# AC_Voltage_Sampling.net
KiCad netlist of a schematic drawn in Altium Designer
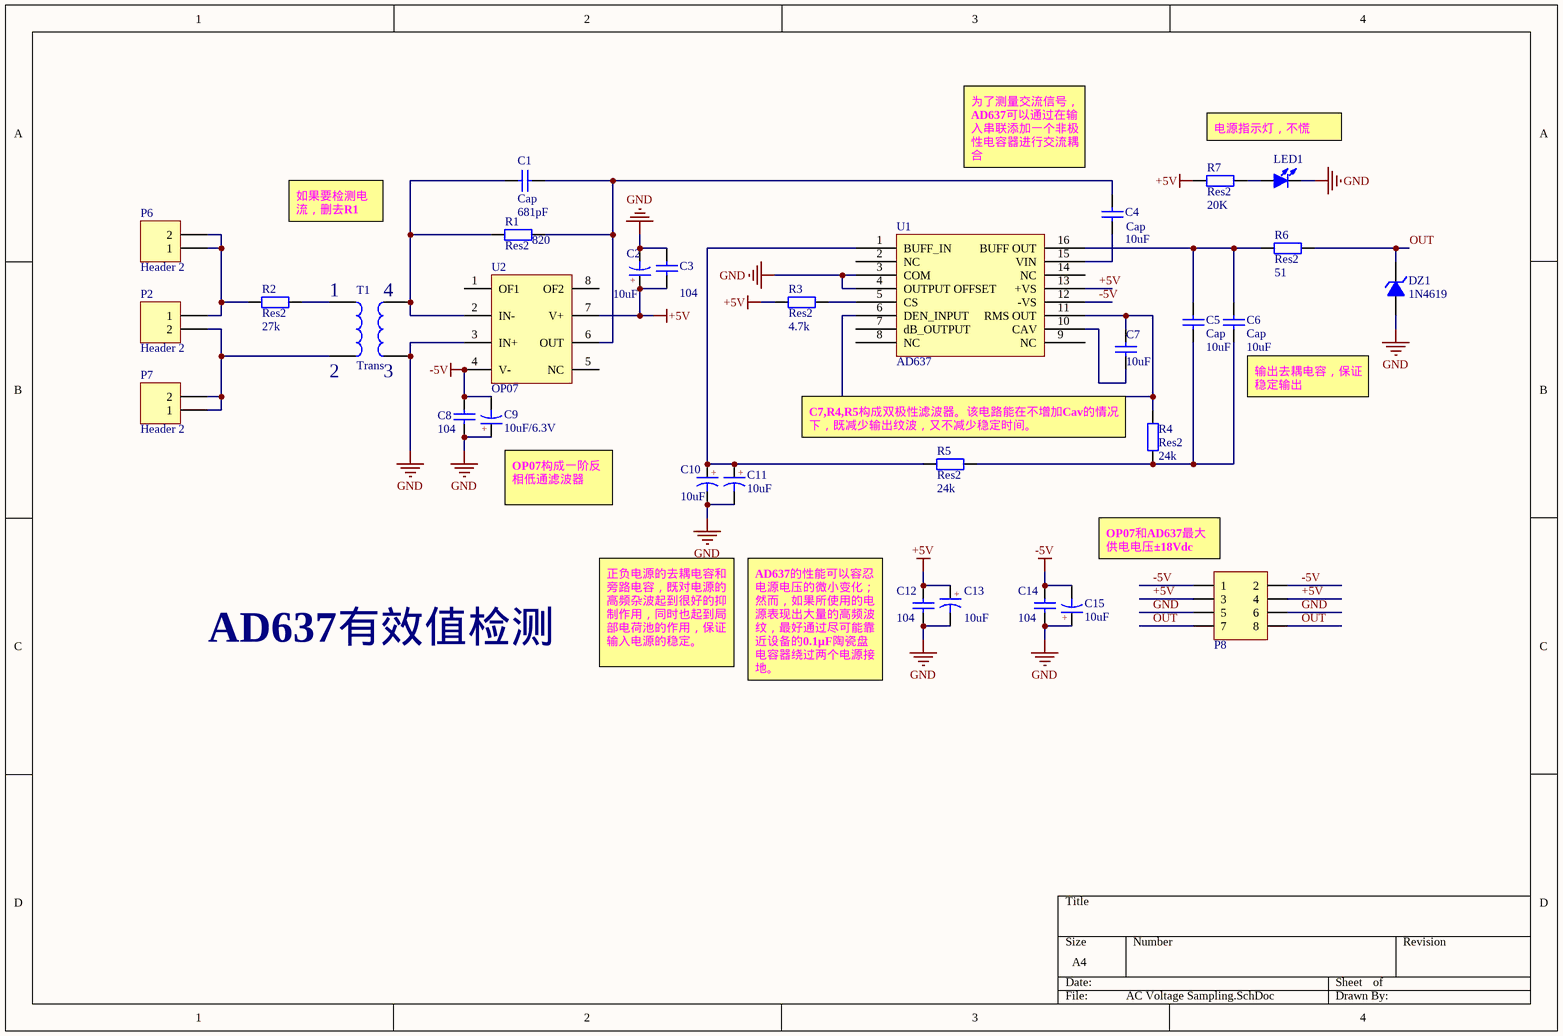
[diagram p0: AC Voltage Sampling.SchDoc]

(export (version "E")
  (design (tool "Eeschema 10.0.6"))
  (components
    (comp (ref "C1")
      (value "Cap")
      (footprint "C0805_L")
      (description "Capacitor")
      (fields (field (name "ALTIUM_VALUE") "681pF") (field (name "PUBLISHER") "Altium Limited"))
      (libsource (lib "Miscellaneous Devices") (part "Cap"))
    )
    (comp (ref "C2")
      (value "10uF")
      (footprint "C_3528")
      (description "贴片钽电容")
      (libsource (lib "0.1 - 电阻-电容-电感-磁珠-电位器") (part "CT"))
    )
    (comp (ref "C3")
      (value "104")
      (footprint "C0805_L")
      (description "Capacitor")
      (fields (field (name "Comment") "Cap") (field (name "PUBLISHER") "Altium Limited"))
      (libsource (lib "Miscellaneous Devices") (part "Cap"))
    )
    (comp (ref "C4")
      (value "Cap")
      (footprint "C0805_L")
      (description "Capacitor")
      (fields (field (name "ALTIUM_VALUE") "10uF") (field (name "PUBLISHER") "Altium Limited"))
      (libsource (lib "Miscellaneous Devices") (part "Cap"))
    )
    (comp (ref "C5")
      (value "Cap")
      (footprint "C0805_L")
      (description "Capacitor")
      (fields (field (name "ALTIUM_VALUE") "10uF") (field (name "PUBLISHER") "Altium Limited"))
      (libsource (lib "Miscellaneous Devices") (part "Cap"))
    )
    (comp (ref "C6")
      (value "Cap")
      (footprint "C0805_L")
      (description "Capacitor")
      (fields (field (name "ALTIUM_VALUE") "10uF") (field (name "PUBLISHER") "Altium Limited"))
      (libsource (lib "Miscellaneous Devices") (part "Cap"))
    )
    (comp (ref "C7")
      (value "10uF")
      (footprint "C0805_L")
      (description "Capacitor")
      (fields (field (name "Comment") "Cap") (field (name "PUBLISHER") "Altium Limited"))
      (libsource (lib "Miscellaneous Devices") (part "Cap"))
    )
    (comp (ref "C8")
      (value "104")
      (footprint "C0805_L")
      (description "Capacitor")
      (fields (field (name "Comment") "Cap") (field (name "PUBLISHER") "Altium Limited"))
      (libsource (lib "Miscellaneous Devices") (part "Cap"))
    )
    (comp (ref "C9")
      (value "10uF/6.3V")
      (footprint "C_3528")
      (description "贴片钽电容")
      (libsource (lib "0.1 - 电阻-电容-电感-磁珠-电位器") (part "CT"))
    )
    (comp (ref "C10")
      (value "10uF")
      (footprint "C_3528")
      (description "贴片钽电容")
      (libsource (lib "0.1 - 电阻-电容-电感-磁珠-电位器") (part "CT"))
    )
    (comp (ref "C11")
      (value "10uF")
      (footprint "C_3528")
      (description "贴片钽电容")
      (libsource (lib "0.1 - 电阻-电容-电感-磁珠-电位器") (part "CT"))
    )
    (comp (ref "C12")
      (value "104")
      (footprint "C0805_L")
      (description "Capacitor")
      (fields (field (name "Comment") "Cap") (field (name "PUBLISHER") "Altium Limited"))
      (libsource (lib "Miscellaneous Devices") (part "Cap"))
    )
    (comp (ref "C13")
      (value "10uF")
      (footprint "C_3528")
      (description "贴片钽电容")
      (libsource (lib "0.1 - 电阻-电容-电感-磁珠-电位器") (part "CT"))
    )
    (comp (ref "C14")
      (value "104")
      (footprint "C0805_L")
      (description "Capacitor")
      (fields (field (name "Comment") "Cap") (field (name "PUBLISHER") "Altium Limited"))
      (libsource (lib "Miscellaneous Devices") (part "Cap"))
    )
    (comp (ref "C15")
      (value "10uF")
      (footprint "C_3528")
      (description "贴片钽电容")
      (libsource (lib "0.1 - 电阻-电容-电感-磁珠-电位器") (part "CT"))
    )
    (comp (ref "DZ1")
      (value "1N4619")
      (footprint "SOD80")
      (description "3V/0.5W稳压管")
      (libsource (lib "0.2 - 二极管-TVS-ESD-整流桥") (part "1N4619"))
    )
    (comp (ref "LED1")
      (value "~")
      (footprint "LED0805_G")
      (description "贴片LED")
      (libsource (lib "0.3 - LED发光二极管") (part "LED-SMD"))
    )
    (comp (ref "P2")
      (value "Header 2")
      (footprint "KF301-5.0-2P")
      (description "Header, 2-Pin")
      (fields (field (name "PUBLISHER") "Altium Limited"))
      (libsource (lib "Miscellaneous Connectors") (part "Header 2"))
    )
    (comp (ref "P6")
      (value "Header 2")
      (footprint "HDR2.54-LI-2P")
      (description "Header, 2-Pin")
      (fields (field (name "PUBLISHER") "Altium Limited"))
      (libsource (lib "") (part "Header 2_1"))
    )
    (comp (ref "P7")
      (value "Header 2")
      (footprint "HDR2.54-LI-2P")
      (description "Header, 2-Pin")
      (fields (field (name "PUBLISHER") "Altium Limited"))
      (libsource (lib "") (part "Header 2_1"))
    )
    (comp (ref "P8")
      (value "Header 4X2")
      (footprint "HDR2.54-LI-2x4P")
      (description "4*2P接插件")
      (libsource (lib "5.5 - 接插件-脚距2.54 (100mil) ") (part "Header 4X2"))
    )
    (comp (ref "R1")
      (value "Res2")
      (footprint "R0805_L")
      (description "Resistor")
      (fields (field (name "ALTIUM_VALUE") "820") (field (name "PUBLISHER") "Altium Limited"))
      (libsource (lib "") (part "Res2_2"))
    )
    (comp (ref "R2")
      (value "Res2")
      (footprint "R0805_L")
      (description "Resistor")
      (fields (field (name "ALTIUM_VALUE") "27k") (field (name "PUBLISHER") "Altium Limited"))
      (libsource (lib "Miscellaneous Devices") (part "Res2"))
    )
    (comp (ref "R3")
      (value "Res2")
      (footprint "R0805_L")
      (description "Resistor")
      (fields (field (name "ALTIUM_VALUE") "4.7k") (field (name "PUBLISHER") "Altium Limited"))
      (libsource (lib "Miscellaneous Devices") (part "Res2"))
    )
    (comp (ref "R4")
      (value "Res2")
      (footprint "R0805_L")
      (description "Resistor")
      (fields (field (name "ALTIUM_VALUE") "24k") (field (name "PUBLISHER") "Altium Limited"))
      (libsource (lib "") (part "Res2_1"))
    )
    (comp (ref "R5")
      (value "Res2")
      (footprint "R0805_L")
      (description "Resistor")
      (fields (field (name "ALTIUM_VALUE") "24k") (field (name "PUBLISHER") "Altium Limited"))
      (libsource (lib "Miscellaneous Devices") (part "Res2"))
    )
    (comp (ref "R6")
      (value "Res2")
      (footprint "R0805_L")
      (description "Resistor")
      (fields (field (name "ALTIUM_VALUE") "51") (field (name "PUBLISHER") "Altium Limited"))
      (libsource (lib "Miscellaneous Devices") (part "Res2"))
    )
    (comp (ref "R7")
      (value "Res2")
      (footprint "R0805_L")
      (description "Resistor")
      (fields (field (name "ALTIUM_VALUE") "20K") (field (name "PUBLISHER") "Altium Limited"))
      (libsource (lib "Miscellaneous Devices") (part "Res2"))
    )
    (comp (ref "T1")
      (value "Trans")
      (footprint "TV1013")
      (description "Transformer")
      (fields (field (name "PUBLISHER") "Altium Limited"))
      (libsource (lib "Miscellaneous Devices") (part "Trans"))
    )
    (comp (ref "U1")
      (value "AD637")
      (footprint "SOIC-16W")
      (description "16脚贴片")
      (libsource (lib "1.6 - ADI系列精密运放") (part "AD637(16p)"))
    )
    (comp (ref "U2") (value "OP07") (footprint "SOP8") (libsource (lib "My schlib") (part "OP07")))
  )
  (nets
    (net (code "1") (name "+5V") (class "Default")
      (node (ref "C12") (pin "1") (pinfunction "1_1") (pintype "passive"))
      (node (ref "C13") (pin "1") (pinfunction "A_1") (pintype "passive"))
      (node (ref "C2") (pin "1") (pinfunction "A_1") (pintype "passive"))
      (node (ref "C3") (pin "1") (pinfunction "1_1") (pintype "passive"))
      (node (ref "P8") (pin "3") (pinfunction "3_3") (pintype "passive"))
      (node (ref "P8") (pin "4") (pinfunction "4_4") (pintype "passive"))
      (node (ref "R3") (pin "1") (pinfunction "1_1") (pintype "passive"))
      (node (ref "R7") (pin "1") (pinfunction "1_1") (pintype "passive"))
      (node (ref "U1") (pin "13") (pinfunction "+VS_13") (pintype "passive"))
      (node (ref "U2") (pin "7") (pinfunction "V+_7") (pintype "passive"))
    )
    (net (code "2") (name "-5V") (class "Default")
      (node (ref "C14") (pin "1") (pinfunction "1_1") (pintype "passive"))
      (node (ref "C15") (pin "2") (pinfunction "K_2") (pintype "passive"))
      (node (ref "C8") (pin "2") (pinfunction "2_2") (pintype "passive"))
      (node (ref "C9") (pin "2") (pinfunction "K_2") (pintype "passive"))
      (node (ref "P8") (pin "1") (pinfunction "1_1") (pintype "passive"))
      (node (ref "P8") (pin "2") (pinfunction "2_2") (pintype "passive"))
      (node (ref "U1") (pin "12") (pinfunction "-VS_12") (pintype "passive"))
      (node (ref "U2") (pin "4") (pinfunction "V-_4") (pintype "passive"))
    )
    (net (code "3") (name "/OUT") (class "Default")
      (node (ref "DZ1") (pin "2") (pinfunction "K_2") (pintype "passive"))
      (node (ref "P8") (pin "7") (pinfunction "7_7") (pintype "passive"))
      (node (ref "P8") (pin "8") (pinfunction "8_8") (pintype "passive"))
      (node (ref "R6") (pin "2") (pinfunction "2_2") (pintype "passive"))
    )
    (net (code "4") (name "GND") (class "Default")
      (node (ref "C10") (pin "2") (pinfunction "K_2") (pintype "passive"))
      (node (ref "C11") (pin "2") (pinfunction "K_2") (pintype "passive"))
      (node (ref "C12") (pin "2") (pinfunction "2_2") (pintype "passive"))
      (node (ref "C13") (pin "2") (pinfunction "K_2") (pintype "passive"))
      (node (ref "C14") (pin "2") (pinfunction "2_2") (pintype "passive"))
      (node (ref "C15") (pin "1") (pinfunction "A_1") (pintype "passive"))
      (node (ref "C2") (pin "2") (pinfunction "K_2") (pintype "passive"))
      (node (ref "C3") (pin "2") (pinfunction "2_2") (pintype "passive"))
      (node (ref "C8") (pin "1") (pinfunction "1_1") (pintype "passive"))
      (node (ref "C9") (pin "1") (pinfunction "A_1") (pintype "passive"))
      (node (ref "DZ1") (pin "1") (pinfunction "A_1") (pintype "passive"))
      (node (ref "LED1") (pin "2") (pinfunction "K_2") (pintype "passive"))
      (node (ref "P8") (pin "5") (pinfunction "5_5") (pintype "passive"))
      (node (ref "P8") (pin "6") (pinfunction "6_6") (pintype "passive"))
      (node (ref "T1") (pin "4") (pinfunction "4_4") (pintype "passive"))
      (node (ref "U1") (pin "3") (pinfunction "COM_3") (pintype "passive"))
      (node (ref "U1") (pin "4") (pinfunction "OUTPUT_OFFSET_4") (pintype "passive"))
      (node (ref "U2") (pin "3") (pinfunction "IN+_3") (pintype "passive"))
    )
    (net (code "5") (name "Net-(C5-Pad1)") (class "Default")
      (node (ref "C5") (pin "1") (pinfunction "1_1") (pintype "passive"))
      (node (ref "C6") (pin "1") (pinfunction "1_1") (pintype "passive"))
      (node (ref "R4") (pin "1") (pinfunction "1_1") (pintype "passive"))
      (node (ref "R5") (pin "2") (pinfunction "2_2") (pintype "passive"))
    )
    (net (code "6") (name "Net-(C10-A)") (class "Default")
      (node (ref "C10") (pin "1") (pinfunction "A_1") (pintype "passive"))
      (node (ref "C11") (pin "1") (pinfunction "A_1") (pintype "passive"))
      (node (ref "R5") (pin "1") (pinfunction "1_1") (pintype "passive"))
      (node (ref "U1") (pin "1") (pinfunction "BUFF_IN_1") (pintype "passive"))
    )
    (net (code "7") (name "Net-(LED1-A)") (class "Default")
      (node (ref "LED1") (pin "1") (pinfunction "A_1") (pintype "passive"))
      (node (ref "R7") (pin "2") (pinfunction "2_2") (pintype "passive"))
    )
    (net (code "8") (name "Net-(P2-Pad1)") (class "Default")
      (node (ref "P2") (pin "1") (pinfunction "1_1") (pintype "passive"))
      (node (ref "P6") (pin "1") (pinfunction "1_1") (pintype "passive"))
      (node (ref "P6") (pin "2") (pinfunction "2_2") (pintype "passive"))
      (node (ref "R2") (pin "1") (pinfunction "1_1") (pintype "passive"))
    )
    (net (code "9") (name "Net-(P2-Pad2)") (class "Default")
      (node (ref "P2") (pin "2") (pinfunction "2_2") (pintype "passive"))
      (node (ref "P7") (pin "1") (pinfunction "1_1") (pintype "passive"))
      (node (ref "P7") (pin "2") (pinfunction "2_2") (pintype "passive"))
      (node (ref "T1") (pin "2") (pinfunction "2_2") (pintype "passive"))
    )
    (net (code "10") (name "Net-(R2-Pad2)") (class "Default")
      (node (ref "R2") (pin "2") (pinfunction "2_2") (pintype "passive"))
      (node (ref "T1") (pin "1") (pinfunction "1_1") (pintype "passive"))
    )
    (net (code "11") (name "Net-(U1-BUFF_OUT)") (class "Default")
      (node (ref "C5") (pin "2") (pinfunction "2_2") (pintype "passive"))
      (node (ref "C6") (pin "2") (pinfunction "2_2") (pintype "passive"))
      (node (ref "R6") (pin "1") (pinfunction "1_1") (pintype "passive"))
      (node (ref "U1") (pin "16") (pinfunction "BUFF_OUT_16") (pintype "passive"))
    )
    (net (code "12") (name "Net-(U1-CAV)") (class "Default")
      (node (ref "C7") (pin "1") (pinfunction "1_1") (pintype "passive"))
      (node (ref "U1") (pin "10") (pinfunction "CAV_10") (pintype "passive"))
    )
    (net (code "13") (name "Net-(U1-CS)") (class "Default")
      (node (ref "R3") (pin "2") (pinfunction "2_2") (pintype "passive"))
      (node (ref "U1") (pin "5") (pinfunction "CS_5") (pintype "passive"))
    )
    (net (code "14") (name "Net-(U1-DEN_INPUT)") (class "Default")
      (node (ref "C7") (pin "2") (pinfunction "2_2") (pintype "passive"))
      (node (ref "R4") (pin "2") (pinfunction "2_2") (pintype "passive"))
      (node (ref "U1") (pin "11") (pinfunction "RMS_OUT_11") (pintype "passive"))
      (node (ref "U1") (pin "6") (pinfunction "DEN_INPUT_6") (pintype "passive"))
    )
    (net (code "15") (name "Net-(U1-VIN)") (class "Default")
      (node (ref "C4") (pin "2") (pinfunction "2_2") (pintype "passive"))
      (node (ref "U1") (pin "15") (pinfunction "VIN_15") (pintype "passive"))
    )
    (net (code "16") (name "Net-(U2-IN-)") (class "Default")
      (node (ref "C1") (pin "1") (pinfunction "1_1") (pintype "passive"))
      (node (ref "R1") (pin "2") (pinfunction "2_2") (pintype "passive"))
      (node (ref "T1") (pin "3") (pinfunction "3_3") (pintype "passive"))
      (node (ref "U2") (pin "2") (pinfunction "IN-_2") (pintype "passive"))
    )
    (net (code "17") (name "Net-(U2-OUT)") (class "Default")
      (node (ref "C1") (pin "2") (pinfunction "2_2") (pintype "passive"))
      (node (ref "C4") (pin "1") (pinfunction "1_1") (pintype "passive"))
      (node (ref "R1") (pin "1") (pinfunction "1_1") (pintype "passive"))
      (node (ref "U2") (pin "6") (pinfunction "OUT_6") (pintype "passive"))
    )
    (net (code "18") (name "unconnected-(U1-NC-Pad2)") (class "Default")
      (node (ref "U1") (pin "2") (pinfunction "NC_2") (pintype "passive"))
    )
    (net (code "19") (name "unconnected-(U1-NC-Pad8)") (class "Default")
      (node (ref "U1") (pin "8") (pinfunction "NC_8") (pintype "passive"))
    )
    (net (code "20") (name "unconnected-(U1-NC-Pad9)") (class "Default")
      (node (ref "U1") (pin "9") (pinfunction "NC_9") (pintype "passive"))
    )
    (net (code "21") (name "unconnected-(U1-NC-Pad14)") (class "Default")
      (node (ref "U1") (pin "14") (pinfunction "NC_14") (pintype "passive"))
    )
    (net (code "22") (name "unconnected-(U1-dB_OUTPUT-Pad7)") (class "Default")
      (node (ref "U1") (pin "7") (pinfunction "dB_OUTPUT_7") (pintype "passive"))
    )
    (net (code "23") (name "unconnected-(U2-NC-Pad5)") (class "Default")
      (node (ref "U2") (pin "5") (pinfunction "NC_5") (pintype "passive"))
    )
    (net (code "24") (name "unconnected-(U2-OF1-Pad1)") (class "Default")
      (node (ref "U2") (pin "1") (pinfunction "OF1_1") (pintype "passive"))
    )
    (net (code "25") (name "unconnected-(U2-OF2-Pad8)") (class "Default")
      (node (ref "U2") (pin "8") (pinfunction "OF2_8") (pintype "passive"))
    )
  )
)
